# Underwater_vehicle.net
KiCad netlist of a schematic drawn in Altium Designer
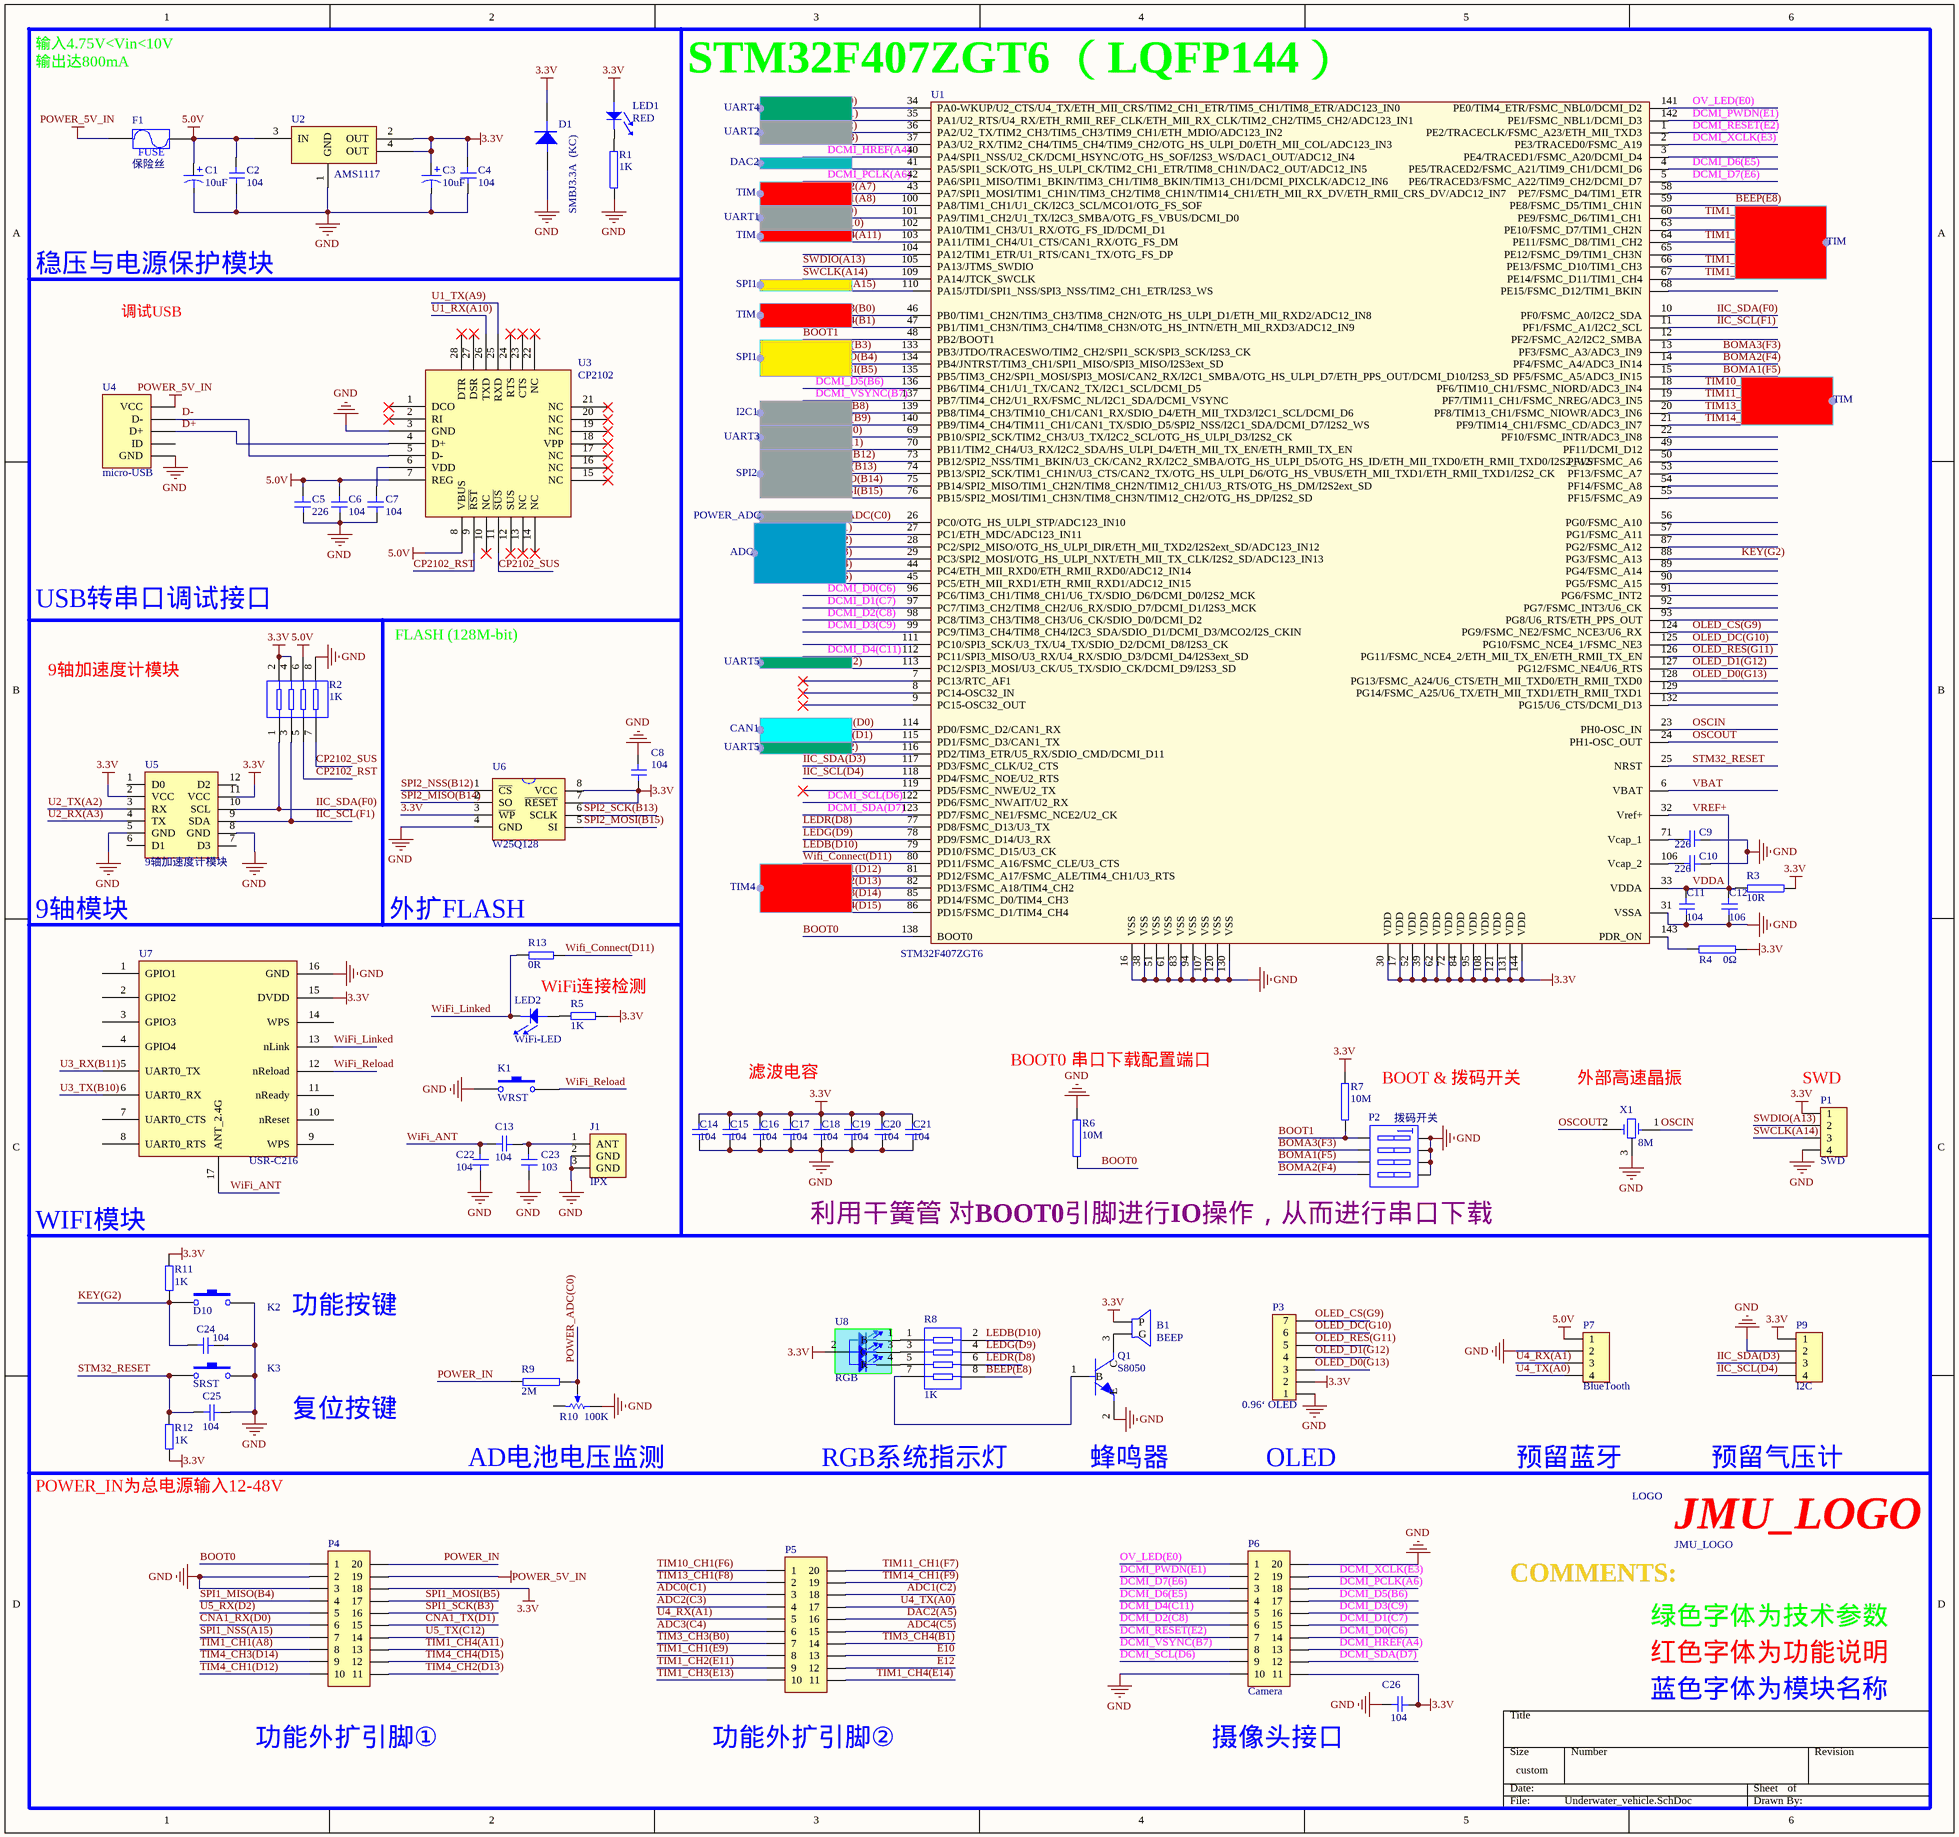
[diagram p0: Underwater_vehicle.SchDoc]

(export (version "E")
  (design (tool "Eeschema 10.0.6"))
  (components
    (comp (ref "B1") (value "BEEP") (footprint "BUZZER") (libsource (lib "EXPLORER") (part "BEEP")))
    (comp (ref "C1")
      (value "10uF")
      (footprint "TAJ-A")
      (description "极性贴片电容")
      (libsource (lib "集大电协1.1.0") (part "Pol Cap"))
    )
    (comp (ref "C2")
      (value "104")
      (footprint "0805C")
      (description "无极贴片电容")
      (libsource (lib "集大电协1.1.0") (part "Cap1"))
    )
    (comp (ref "C3")
      (value "10uF")
      (footprint "TAJ-A")
      (description "极性贴片电容")
      (libsource (lib "集大电协1.1.0") (part "Pol Cap"))
    )
    (comp (ref "C4")
      (value "104")
      (footprint "0805C")
      (description "无极贴片电容")
      (libsource (lib "集大电协1.1.0") (part "Cap1"))
    )
    (comp (ref "C5")
      (value "226")
      (footprint "0805C")
      (description "无极贴片电容")
      (libsource (lib "集大电协1.1.0") (part "Cap1"))
    )
    (comp (ref "C6")
      (value "104")
      (footprint "0805C")
      (description "无极贴片电容")
      (libsource (lib "集大电协1.1.0") (part "Cap1"))
    )
    (comp (ref "C7")
      (value "104")
      (footprint "0805C")
      (description "无极贴片电容")
      (libsource (lib "集大电协1.1.0") (part "Cap1"))
    )
    (comp (ref "C8")
      (value "104")
      (footprint "0805C")
      (description "无极贴片电容")
      (libsource (lib "集大电协1.1.0") (part "Cap1"))
    )
    (comp (ref "C9") (value "226") (footprint "0805C") (libsource (lib "窝牛器件封装") (part "C1")))
    (comp (ref "C10") (value "226") (footprint "0805C") (libsource (lib "窝牛器件封装") (part "C1")))
    (comp (ref "C11") (value "104") (footprint "0805C") (libsource (lib "窝牛器件封装") (part "C1")))
    (comp (ref "C12") (value "106") (footprint "0805C") (libsource (lib "窝牛器件封装") (part "C1")))
    (comp (ref "C13")
      (value "104")
      (footprint "0805C")
      (description "无极贴片电容")
      (libsource (lib "集大电协1.1.2") (part "Cap1"))
    )
    (comp (ref "C14") (value "104") (footprint "0805C") (libsource (lib "窝牛器件封装") (part "C1")))
    (comp (ref "C15") (value "104") (footprint "0805C") (libsource (lib "窝牛器件封装") (part "C1")))
    (comp (ref "C16") (value "104") (footprint "0805C") (libsource (lib "窝牛器件封装") (part "C1")))
    (comp (ref "C17") (value "104") (footprint "0805C") (libsource (lib "窝牛器件封装") (part "C1")))
    (comp (ref "C18") (value "104") (footprint "0805C") (libsource (lib "窝牛器件封装") (part "C1")))
    (comp (ref "C19") (value "104") (footprint "0805C") (libsource (lib "窝牛器件封装") (part "C1")))
    (comp (ref "C20") (value "104") (footprint "0805C") (libsource (lib "窝牛器件封装") (part "C1")))
    (comp (ref "C21") (value "104") (footprint "0805C") (libsource (lib "窝牛器件封装") (part "C1")))
    (comp (ref "C22")
      (value "104")
      (footprint "0805C")
      (description "无极贴片电容")
      (libsource (lib "集大电协1.1.2") (part "Cap1"))
    )
    (comp (ref "C23")
      (value "103")
      (footprint "0805C")
      (description "无极贴片电容")
      (libsource (lib "集大电协1.1.2") (part "Cap1"))
    )
    (comp (ref "C24") (value "104") (footprint "0805C") (libsource (lib "窝牛器件封装") (part "C1")))
    (comp (ref "C25") (value "104") (footprint "0805C") (libsource (lib "窝牛器件封装") (part "C1")))
    (comp (ref "C26")
      (value "104")
      (footprint "0805C")
      (description "无极贴片电容")
      (libsource (lib "集大电协1.1.5") (part "Cap1"))
    )
    (comp (ref "D1")
      (value "SMBJ3.3A  (KC)")
      (footprint "SMBJ")
      (description "二极管")
      (libsource (lib "集大电协1.1.0") (part "Diode"))
    )
    (comp (ref "F1") (value "保险丝") (footprint "1812") (libsource (lib "集大电协1.1.2") (part "Fuse")))
    (comp (ref "J1") (value "IPX") (footprint "IPX天线底座") (libsource (lib "集大电协1.1.2") (part "IPX天线座")))
    (comp (ref "K1")
      (value "WRST")
      (footprint "贴片按键")
      (description "轻触开关")
      (libsource (lib "集大电协1.1.2") (part "轻触按键"))
    )
    (comp (ref "K2") (value "D10") (footprint "贴片按键") (libsource (lib "窝牛器件封装") (part "Key(两脚贴片)")))
    (comp (ref "K3") (value "SRST") (footprint "贴片按键") (libsource (lib "窝牛器件封装") (part "Key(两脚贴片)")))
    (comp (ref "LED1")
      (value "RED")
      (footprint "0805LED(RED)")
      (description "发光二极管")
      (libsource (lib "集大电协1.1.2") (part "LED"))
    )
    (comp (ref "LED2")
      (value "WiFi-LED")
      (footprint "0805LED(GREEN)")
      (description "发光二极管")
      (libsource (lib "集大电协1.1.2") (part "LED"))
    )
    (comp (ref "LOGO")
      (value "JMU_LOGO")
      (footprint "JMU_LOGO(1.35cm)")
      (description "LOGO")
      (libsource (lib "集大电协1.1.5") (part "JMU_LOGO"))
    )
    (comp (ref "P1")
      (value "SWD")
      (footprint "Header 4")
      (description "排针")
      (libsource (lib "集大电协1.1.0") (part "Header 4"))
    )
    (comp (ref "P2")
      (value "拨码开关")
      (footprint "拨码开关(4位贴片)")
      (description "4位拨码开关")
      (libsource (lib "集大电协1.1.2") (part "拨码开关4"))
    )
    (comp (ref "P3")
      (value "0.96‘ OLED")
      (footprint "Header 7")
      (description "排针")
      (libsource (lib "集大电协1.1.5") (part "Header 7"))
    )
    (comp (ref "P4") (value "~") (footprint "Header 10X2") (libsource (lib "集大电协1.1.2") (part "Header 10X2")))
    (comp (ref "P5") (value "~") (footprint "Header 10X2") (libsource (lib "集大电协1.1.2") (part "Header 10X2")))
    (comp (ref "P6")
      (value "Camera")
      (footprint "Header 10X2")
      (libsource (lib "集大电协1.1.2") (part "Header 10X2"))
    )
    (comp (ref "P7")
      (value "BlueTooth")
      (footprint "Header 4(排母)")
      (description "排针")
      (libsource (lib "集大电协1.1.5") (part "Header 4"))
    )
    (comp (ref "P9")
      (value "I2C")
      (footprint "Header 4")
      (description "排针")
      (libsource (lib "集大电协1.1.5") (part "Header 4"))
    )
    (comp (ref "Q1")
      (value "S8050")
      (footprint "SOT-23")
      (description "NPN三极管")
      (libsource (lib "集大电协1.1.2") (part "NPN"))
    )
    (comp (ref "R1") (value "1K") (footprint "0805R") (libsource (lib "窝牛器件封装") (part "R1")))
    (comp (ref "R2")
      (value "1K")
      (footprint "排阻(4位贴片)")
      (description "排阻")
      (libsource (lib "集大电协1.1.2") (part "Res-4"))
    )
    (comp (ref "R3") (value "10R") (footprint "0805R") (libsource (lib "窝牛器件封装") (part "R1")))
    (comp (ref "R4") (value "0Ω") (footprint "0805R") (libsource (lib "窝牛器件封装") (part "R1")))
    (comp (ref "R5")
      (value "1K")
      (footprint "0805R")
      (description "电阻")
      (libsource (lib "集大电协1.1.2") (part "Res"))
    )
    (comp (ref "R6") (value "10M") (footprint "0805R") (libsource (lib "窝牛器件封装") (part "R1")))
    (comp (ref "R7") (value "10M") (footprint "0805R") (libsource (lib "窝牛器件封装") (part "R1")))
    (comp (ref "R8")
      (value "1K")
      (footprint "排阻(4位贴片)")
      (description "排阻")
      (libsource (lib "集大电协1.1.2") (part "Res-4"))
    )
    (comp (ref "R9") (value "2M") (footprint "0805R") (libsource (lib "窝牛器件封装") (part "R1")))
    (comp (ref "R10")
      (value "100K")
      (footprint "3296w")
      (description "电位器")
      (libsource (lib "集大电协1.1.2") (part "RPot"))
    )
    (comp (ref "R11")
      (value "1K")
      (footprint "0805R")
      (description "电阻")
      (libsource (lib "集大电协1.1.5") (part "Res"))
    )
    (comp (ref "R12")
      (value "1K")
      (footprint "0805R")
      (description "电阻")
      (libsource (lib "集大电协1.1.5") (part "Res"))
    )
    (comp (ref "R13")
      (value "0R")
      (footprint "0805R")
      (description "电阻")
      (libsource (lib "集大电协1.1.5") (part "Res"))
    )
    (comp (ref "U1")
      (value "STM32F407ZGT6")
      (footprint "LQFP-144")
      (libsource (lib "窝牛器件封装") (part "STM32F407ZET6"))
    )
    (comp (ref "U2")
      (value "AMS1117")
      (footprint "SOT-223")
      (description "电源芯片")
      (libsource (lib "集大电协1.1.0") (part "AMS1117-3.3V/5.0V"))
    )
    (comp (ref "U3")
      (value "CP2102")
      (footprint "QFN-28")
      (description "USB转串口芯片")
      (libsource (lib "集大电协1.1.0") (part "CP2102"))
    )
    (comp (ref "U4")
      (value "micro-USB")
      (footprint "Micro-USB (兼容牛角)")
      (description "USB接口")
      (libsource (lib "集大电协1.1.2") (part "micro-USB"))
    )
    (comp (ref "U5") (value "9轴加速度计模块") (footprint "9轴加速度计") (libsource (lib "窝牛器件封装") (part "9轴加速度计")))
    (comp (ref "U6")
      (value "W25Q128")
      (footprint "SOW-8")
      (description "FLASH芯片")
      (libsource (lib "集大电协1.1.0") (part "W25Q128"))
    )
    (comp (ref "U7")
      (value "USR-C216")
      (footprint "USR-C216")
      (libsource (lib "集大电协1.1.2") (part "USR-C216"))
    )
    (comp (ref "U8") (value "RGB") (footprint "RGB-3528") (libsource (lib "集大电协1.1.2") (part "RGB")))
    (comp (ref "X1") (value "8M") (footprint "三脚贴片8M晶振") (libsource (lib "集大电协1.1.2") (part "XTAL三脚贴片晶振")))
  )
  (nets
    (net (code "1") (name "/ADC0(C1)") (class "Default")
      (node (ref "P5") (pin "3") (pinfunction "3_3") (pintype "passive"))
      (node (ref "U1") (pin "27") (pinfunction "PC1/ETH_MDC/ADC123_IN11_27") (pintype "passive"))
    )
    (net (code "2") (name "/ADC1(C2)") (class "Default")
      (node (ref "P5") (pin "18") (pinfunction "18_18") (pintype "passive"))
      (node (ref "U1") (pin "28") (pinfunction "PC2/SPI2_MISO/OTG_HS_ULPI_DIR/ETH_MII_TXD2/I2S2ext_SD/ADC123_IN12_28") (pintype "passive"))
    )
    (net (code "3") (name "/ADC2(C3)") (class "Default")
      (node (ref "P5") (pin "4") (pinfunction "4_4") (pintype "passive"))
      (node (ref "U1") (pin "29") (pinfunction "PC3/SPI2_MOSI/OTG_HS_ULPI_NXT/ETH_MII_TX_CLK/I2S2_SD/ADC123_IN13_29") (pintype "passive"))
    )
    (net (code "4") (name "/ADC3(C4)") (class "Default")
      (node (ref "P5") (pin "6") (pinfunction "6_6") (pintype "passive"))
      (node (ref "U1") (pin "44") (pinfunction "PC4/ETH_MII_RXD0/ETH_RMII_RXD0/ADC12_IN14_44") (pintype "passive"))
    )
    (net (code "5") (name "/ADC4(C5)") (class "Default")
      (node (ref "P5") (pin "15") (pinfunction "15_15") (pintype "passive"))
      (node (ref "U1") (pin "45") (pinfunction "PC5/ETH_MII_RXD1/ETH_RMII_RXD1/ADC12_IN15_45") (pintype "passive"))
    )
    (net (code "6") (name "/BEEP(E8)") (class "Default")
      (node (ref "R8") (pin "8") (pinfunction "8_8") (pintype "passive"))
      (node (ref "U1") (pin "59") (pinfunction "PE8/FSMC_D5/TIM1_CH1N_59") (pintype "passive"))
    )
    (net (code "7") (name "/BOMA1(F5)") (class "Default")
      (node (ref "P2") (pin "3") (pinfunction "A3_3") (pintype "passive"))
      (node (ref "U1") (pin "15") (pinfunction "PF5/FSMC_A5/ADC3_IN15_15") (pintype "passive"))
    )
    (net (code "8") (name "/BOMA2(F4)") (class "Default")
      (node (ref "P2") (pin "4") (pinfunction "A4_4") (pintype "passive"))
      (node (ref "U1") (pin "14") (pinfunction "PF4/FSMC_A4/ADC3_IN14_14") (pintype "passive"))
    )
    (net (code "9") (name "/BOMA3(F3)") (class "Default")
      (node (ref "P2") (pin "2") (pinfunction "A2_2") (pintype "passive"))
      (node (ref "U1") (pin "13") (pinfunction "PF3/FSMC_A3/ADC3_IN9_13") (pintype "passive"))
    )
    (net (code "10") (name "/BOOT0") (class "Default")
      (node (ref "P4") (pin "1") (pinfunction "1_1") (pintype "passive"))
      (node (ref "R6") (pin "1") (pinfunction "1_1") (pintype "passive"))
      (node (ref "U1") (pin "138") (pinfunction "BOOT0_138") (pintype "passive"))
    )
    (net (code "11") (name "/BOOT1") (class "Default")
      (node (ref "P2") (pin "1") (pinfunction "A1_1") (pintype "passive"))
      (node (ref "R7") (pin "1") (pinfunction "1_1") (pintype "passive"))
      (node (ref "U1") (pin "48") (pinfunction "PB2/BOOT1_48") (pintype "passive"))
    )
    (net (code "12") (name "/CNA1_RX(D0)") (class "Default")
      (node (ref "P4") (pin "6") (pinfunction "6_6") (pintype "passive"))
      (node (ref "U1") (pin "114") (pinfunction "PD0/FSMC_D2/CAN1_RX_114") (pintype "passive"))
    )
    (net (code "13") (name "/CNA1_TX(D1)") (class "Default")
      (node (ref "P4") (pin "15") (pinfunction "15_15") (pintype "passive"))
      (node (ref "U1") (pin "115") (pinfunction "PD1/FSMC_D3/CAN1_TX_115") (pintype "passive"))
    )
    (net (code "14") (name "/CP2102_RST") (class "Default")
      (node (ref "R2") (pin "5") (pinfunction "5_5") (pintype "passive"))
      (node (ref "U3") (pin "9") (pinfunction "~{RST}_9") (pintype "passive"))
    )
    (net (code "15") (name "/CP2102_SUS") (class "Default")
      (node (ref "R2") (pin "7") (pinfunction "7_7") (pintype "passive"))
      (node (ref "U3") (pin "11") (pinfunction "~{SUS}_11") (pintype "passive"))
    )
    (net (code "16") (name "/D+") (class "Default")
      (node (ref "U3") (pin "4") (pinfunction "D+_4") (pintype "passive"))
      (node (ref "U4") (pin "3") (pinfunction "D+_3") (pintype "power_in"))
    )
    (net (code "17") (name "/D-") (class "Default")
      (node (ref "U3") (pin "5") (pinfunction "D-_5") (pintype "passive"))
      (node (ref "U4") (pin "2") (pinfunction "D-_2") (pintype "power_in"))
    )
    (net (code "18") (name "/DAC2(A5)") (class "Default")
      (node (ref "P5") (pin "16") (pinfunction "16_16") (pintype "passive"))
      (node (ref "U1") (pin "41") (pinfunction "PA5/SPI1_SCK/OTG_HS_ULPI_CK/TIM2_CH1_ETR/TIM8_CH1N/DAC2_OUT/ADC12_IN5_41") (pintype "passive"))
    )
    (net (code "19") (name "/DCMI_D0(C6)") (class "Default")
      (node (ref "P6") (pin "14") (pinfunction "14_14") (pintype "passive"))
      (node (ref "U1") (pin "96") (pinfunction "PC6/TIM3_CH1/TIM8_CH1/U6_TX/SDIO_D6/DCMI_D0/I2S2_MCK_96") (pintype "passive"))
    )
    (net (code "20") (name "/DCMI_D1(C7)") (class "Default")
      (node (ref "P6") (pin "15") (pinfunction "15_15") (pintype "passive"))
      (node (ref "U1") (pin "97") (pinfunction "PC7/TIM3_CH2/TIM8_CH2/U6_RX/SDIO_D7/DCMI_D1/I2S3_MCK_97") (pintype "passive"))
    )
    (net (code "21") (name "/DCMI_D2(C8)") (class "Default")
      (node (ref "P6") (pin "6") (pinfunction "6_6") (pintype "passive"))
      (node (ref "U1") (pin "98") (pinfunction "PC8/TIM3_CH3/TIM8_CH3/U6_CK/SDIO_D0/DCMI_D2_98") (pintype "passive"))
    )
    (net (code "22") (name "/DCMI_D3(C9)") (class "Default")
      (node (ref "P6") (pin "16") (pinfunction "16_16") (pintype "passive"))
      (node (ref "U1") (pin "99") (pinfunction "PC9/TIM3_CH4/TIM8_CH4/I2C3_SDA/SDIO_D1/DCMI_D3/MCO2/I2S_CKIN_99") (pintype "passive"))
    )
    (net (code "23") (name "/DCMI_D4(C11)") (class "Default")
      (node (ref "P6") (pin "5") (pinfunction "5_5") (pintype "passive"))
      (node (ref "U1") (pin "112") (pinfunction "PC11/SPI3_MISO/U3_RX/U4_RX/SDIO_D3/DCMI_D4/I2S3ext_SD_112") (pintype "passive"))
    )
    (net (code "24") (name "/DCMI_D5(B6)") (class "Default")
      (node (ref "P6") (pin "17") (pinfunction "17_17") (pintype "passive"))
      (node (ref "U1") (pin "136") (pinfunction "PB6/TIM4_CH1/U1_TX/CAN2_TX/I2C1_SCL/DCMI_D5_136") (pintype "passive"))
    )
    (net (code "25") (name "/DCMI_D6(E5)") (class "Default")
      (node (ref "P6") (pin "4") (pinfunction "4_4") (pintype "passive"))
      (node (ref "U1") (pin "4") (pinfunction "PE5/TRACED2/FSMC_A21/TIM9_CH1/DCMI_D6_4") (pintype "passive"))
    )
    (net (code "26") (name "/DCMI_D7(E6)") (class "Default")
      (node (ref "P6") (pin "3") (pinfunction "3_3") (pintype "passive"))
      (node (ref "U1") (pin "5") (pinfunction "PE6/TRACED3/FSMC_A22/TIM9_CH2/DCMI_D7_5") (pintype "passive"))
    )
    (net (code "27") (name "/DCMI_HREF(A4)") (class "Default")
      (node (ref "P6") (pin "13") (pinfunction "13_13") (pintype "passive"))
      (node (ref "U1") (pin "40") (pinfunction "PA4/SPI1_NSS/U2_CK/DCMI_HSYNC/OTG_HS_SOF/I2S3_WS/DAC1_OUT/ADC12_IN4_40") (pintype "passive"))
    )
    (net (code "28") (name "/DCMI_PCLK(A6)") (class "Default")
      (node (ref "P6") (pin "18") (pinfunction "18_18") (pintype "passive"))
      (node (ref "U1") (pin "42") (pinfunction "PA6/SPI1_MISO/TIM1_BKIN/TIM3_CH1/TIM8_BKIN/TIM13_CH1/DCMI_PIXCLK/ADC12_IN6_42") (pintype "passive"))
    )
    (net (code "29") (name "/DCMI_PWDN(E1)") (class "Default")
      (node (ref "P6") (pin "2") (pinfunction "2_2") (pintype "passive"))
      (node (ref "U1") (pin "142") (pinfunction "PE1/FSMC_NBL1/DCMI_D3_142") (pintype "passive"))
    )
    (net (code "30") (name "/DCMI_RESET(E2)") (class "Default")
      (node (ref "P6") (pin "7") (pinfunction "7_7") (pintype "passive"))
      (node (ref "U1") (pin "1") (pinfunction "PE2/TRACECLK/FSMC_A23/ETH_MII_TXD3_1") (pintype "passive"))
    )
    (net (code "31") (name "/DCMI_SCL(D6)") (class "Default")
      (node (ref "P6") (pin "9") (pinfunction "9_9") (pintype "passive"))
      (node (ref "U1") (pin "122") (pinfunction "PD6/FSMC_NWAIT/U2_RX_122") (pintype "passive"))
    )
    (net (code "32") (name "/DCMI_SDA(D7)") (class "Default")
      (node (ref "P6") (pin "12") (pinfunction "12_12") (pintype "passive"))
      (node (ref "U1") (pin "123") (pinfunction "PD7/FSMC_NE1/FSMC_NCE2/U2_CK_123") (pintype "passive"))
    )
    (net (code "33") (name "/DCMI_VSYNC(B7)") (class "Default")
      (node (ref "P6") (pin "8") (pinfunction "8_8") (pintype "passive"))
      (node (ref "U1") (pin "137") (pinfunction "PB7/TIM4_CH2/U1_RX/FSMC_NL/I2C1_SDA/DCMI_VSYNC_137") (pintype "passive"))
    )
    (net (code "34") (name "/DCMI_XCLK(E3)") (class "Default")
      (node (ref "P6") (pin "19") (pinfunction "19_19") (pintype "passive"))
      (node (ref "U1") (pin "2") (pinfunction "PE3/TRACED0/FSMC_A19_2") (pintype "passive"))
    )
    (net (code "35") (name "/E10") (class "Default")
      (node (ref "P5") (pin "13") (pinfunction "13_13") (pintype "passive"))
      (node (ref "U1") (pin "63") (pinfunction "PE10/FSMC_D7/TIM1_CH2N_63") (pintype "passive"))
    )
    (net (code "36") (name "/E12") (class "Default")
      (node (ref "P5") (pin "12") (pinfunction "12_12") (pintype "passive"))
      (node (ref "U1") (pin "65") (pinfunction "PE12/FSMC_D9/TIM1_CH3N_65") (pintype "passive"))
    )
    (net (code "37") (name "/IIC1_SCL(B8)") (class "Default")
      (node (ref "U1") (pin "139") (pinfunction "PB8/TIM4_CH3/TIM10_CH1/CAN1_RX/SDIO_D4/ETH_MII_TXD3/I2C1_SCL/DCMI_D6_139") (pintype "passive"))
    )
    (net (code "38") (name "/IIC1_SDA(B9)") (class "Default")
      (node (ref "U1") (pin "140") (pinfunction "PB9/TIM4_CH4/TIM11_CH1/CAN1_TX/SDIO_D5/SPI2_NSS/I2C1_SDA/DCMI_D7/I2S2_WS_140") (pintype "passive"))
    )
    (net (code "39") (name "/IIC_SCL(D4)") (class "Default")
      (node (ref "P9") (pin "4") (pinfunction "4_4") (pintype "passive"))
      (node (ref "U1") (pin "118") (pinfunction "PD4/FSMC_NOE/U2_RTS_118") (pintype "passive"))
    )
    (net (code "40") (name "/IIC_SCL(F1)") (class "Default")
      (node (ref "R2") (pin "3") (pinfunction "3_3") (pintype "passive"))
      (node (ref "U1") (pin "11") (pinfunction "PF1/FSMC_A1/I2C2_SCL_11") (pintype "passive"))
      (node (ref "U5") (pin "9") (pinfunction "SDA_9") (pintype "passive"))
    )
    (net (code "41") (name "/IIC_SDA(D3)") (class "Default")
      (node (ref "P9") (pin "3") (pinfunction "3_3") (pintype "passive"))
      (node (ref "U1") (pin "117") (pinfunction "PD3/FSMC_CLK/U2_CTS_117") (pintype "passive"))
    )
    (net (code "42") (name "/IIC_SDA(F0)") (class "Default")
      (node (ref "R2") (pin "1") (pinfunction "1_1") (pintype "passive"))
      (node (ref "U1") (pin "10") (pinfunction "PF0/FSMC_A0/I2C2_SDA_10") (pintype "passive"))
      (node (ref "U5") (pin "10") (pinfunction "SCL_10") (pintype "passive"))
    )
    (net (code "43") (name "/KEY(G2)") (class "Default")
      (node (ref "C24") (pin "1") (pinfunction "1_1") (pintype "passive"))
      (node (ref "K2") (pin "1") (pinfunction "1_1") (pintype "passive"))
      (node (ref "R11") (pin "1") (pinfunction "1_1") (pintype "passive"))
      (node (ref "U1") (pin "88") (pinfunction "PG3/FSMC_A13_88") (pintype "passive"))
    )
    (net (code "44") (name "/LEDB(D10)") (class "Default")
      (node (ref "R8") (pin "2") (pinfunction "2_2") (pintype "passive"))
      (node (ref "U1") (pin "79") (pinfunction "PD10/FSMC_D15/U3_CK_79") (pintype "passive"))
    )
    (net (code "45") (name "/LEDG(D9)") (class "Default")
      (node (ref "R8") (pin "4") (pinfunction "4_4") (pintype "passive"))
      (node (ref "U1") (pin "78") (pinfunction "PD9/FSMC_D14/U3_RX_78") (pintype "passive"))
    )
    (net (code "46") (name "/LEDR(D8)") (class "Default")
      (node (ref "R8") (pin "6") (pinfunction "6_6") (pintype "passive"))
      (node (ref "U1") (pin "77") (pinfunction "PD8/FSMC_D13/U3_TX_77") (pintype "passive"))
    )
    (net (code "47") (name "/OLED_CS(G9)") (class "Default")
      (node (ref "P3") (pin "7") (pinfunction "7_7") (pintype "passive"))
      (node (ref "U1") (pin "124") (pinfunction "PG9/FSMC_NE2/FSMC_NCE3/U6_RX_124") (pintype "passive"))
    )
    (net (code "48") (name "/OLED_D0(G13)") (class "Default")
      (node (ref "P3") (pin "3") (pinfunction "3_3") (pintype "passive"))
      (node (ref "U1") (pin "128") (pinfunction "PG13/FSMC_A24/U6_CTS/ETH_MII_TXD0/ETH_RMII_TXD0_128") (pintype "passive"))
    )
    (net (code "49") (name "/OLED_D1(G12)") (class "Default")
      (node (ref "P3") (pin "4") (pinfunction "4_4") (pintype "passive"))
      (node (ref "U1") (pin "127") (pinfunction "PG12/FSMC_NE4/U6_RTS_127") (pintype "passive"))
    )
    (net (code "50") (name "/OLED_DC(G10)") (class "Default")
      (node (ref "P3") (pin "6") (pinfunction "6_6") (pintype "passive"))
      (node (ref "U1") (pin "125") (pinfunction "PG10/FSMC_NCE4_1/FSMC_NE3_125") (pintype "passive"))
    )
    (net (code "51") (name "/OLED_RES(G11)") (class "Default")
      (node (ref "P3") (pin "5") (pinfunction "5_5") (pintype "passive"))
      (node (ref "U1") (pin "126") (pinfunction "PG11/FSMC_NCE4_2/ETH_MII_TX_EN/ETH_RMII_TX_EN_126") (pintype "passive"))
    )
    (net (code "52") (name "/OSCIN") (class "Default")
      (node (ref "U1") (pin "23") (pinfunction "PH0-OSC_IN_23") (pintype "passive"))
      (node (ref "X1") (pin "1") (pinfunction "1_1") (pintype "passive"))
    )
    (net (code "53") (name "/OSCOUT") (class "Default")
      (node (ref "U1") (pin "24") (pinfunction "PH1-OSC_OUT_24") (pintype "passive"))
      (node (ref "X1") (pin "2") (pinfunction "2_2") (pintype "passive"))
    )
    (net (code "54") (name "/OV_LED(E0)") (class "Default")
      (node (ref "P6") (pin "1") (pinfunction "1_1") (pintype "passive"))
      (node (ref "U1") (pin "141") (pinfunction "PE0/TIM4_ETR/FSMC_NBL0/DCMI_D2_141") (pintype "passive"))
    )
    (net (code "55") (name "/POWER_ADC(C0)") (class "Default")
      (node (ref "R10") (pin "2") (pinfunction "TAP_2") (pintype "passive"))
      (node (ref "R9") (pin "2") (pinfunction "2_2") (pintype "passive"))
      (node (ref "U1") (pin "26") (pinfunction "PC0/OTG_HS_ULPI_STP/ADC123_IN10_26") (pintype "passive"))
    )
    (net (code "56") (name "/POWER_IN") (class "Default")
      (node (ref "P4") (pin "20") (pinfunction "20_20") (pintype "passive"))
      (node (ref "R9") (pin "1") (pinfunction "1_1") (pintype "passive"))
    )
    (net (code "57") (name "/SPI1_MISO(B4)") (class "Default")
      (node (ref "P4") (pin "4") (pinfunction "4_4") (pintype "passive"))
      (node (ref "U1") (pin "134") (pinfunction "PB4/JNTRST/TIM3_CH1/SPI1_MISO/SPI3_MISO/I2S3ext_SD_134") (pintype "passive"))
    )
    (net (code "58") (name "/SPI1_MOSI(B5)") (class "Default")
      (node (ref "P4") (pin "17") (pinfunction "17_17") (pintype "passive"))
      (node (ref "U1") (pin "135") (pinfunction "PB5/TIM3_CH2/SPI1_MOSI/SPI3_MOSI/CAN2_RX/I2C1_SMBA/OTG_HS_ULPI_D7/ETH_PPS_OUT/DCMI_D10/I2S3_SD_135") (pintype "passive"))
    )
    (net (code "59") (name "/SPI1_NSS(A15)") (class "Default")
      (node (ref "P4") (pin "7") (pinfunction "7_7") (pintype "passive"))
      (node (ref "U1") (pin "110") (pinfunction "PA15/JTDI/SPI1_NSS/SPI3_NSS/TIM2_CH1_ETR/I2S3_WS_110") (pintype "passive"))
    )
    (net (code "60") (name "/SPI1_SCK(B3)") (class "Default")
      (node (ref "P4") (pin "16") (pinfunction "16_16") (pintype "passive"))
      (node (ref "U1") (pin "133") (pinfunction "PB3/JTDO/TRACESWO/TIM2_CH2/SPI1_SCK/SPI3_SCK/I2S3_CK_133") (pintype "passive"))
    )
    (net (code "61") (name "/SPI2_MISO(B14)") (class "Default")
      (node (ref "U1") (pin "75") (pinfunction "PB14/SPI2_MISO/TIM1_CH2N/TIM8_CH2N/TIM12_CH1/U3_RTS/OTG_HS_DM/I2S2ext_SD_75") (pintype "passive"))
      (node (ref "U6") (pin "2") (pinfunction "SO_2") (pintype "passive"))
    )
    (net (code "62") (name "/SPI2_MOSI(B15)") (class "Default")
      (node (ref "U1") (pin "76") (pinfunction "PB15/SPI2_MOSI/TIM1_CH3N/TIM8_CH3N/TIM12_CH2/OTG_HS_DP/I2S2_SD_76") (pintype "passive"))
      (node (ref "U6") (pin "5") (pinfunction "SI_5") (pintype "passive"))
    )
    (net (code "63") (name "/SPI2_NSS(B12)") (class "Default")
      (node (ref "U1") (pin "73") (pinfunction "PB12/SPI2_NSS/TIM1_BKIN/U3_CK/CAN2_RX/I2C2_SMBA/OTG_HS_ULPI_D5/OTG_HS_ID/ETH_MII_TXD0/ETH_RMII_TXD0/I2S2_WS_73") (pintype "passive"))
      (node (ref "U6") (pin "1") (pinfunction "~{CS}_1") (pintype "passive"))
    )
    (net (code "64") (name "/SPI2_SCK(B13)") (class "Default")
      (node (ref "U1") (pin "74") (pinfunction "PB13/SPI2_SCK/TIM1_CH1N/U3_CTS/CAN2_TX/OTG_HS_ULPI_D6/OTG_HS_VBUS/ETH_MII_TXD1/ETH_RMII_TXD1/I2S2_CK_74") (pintype "passive"))
      (node (ref "U6") (pin "6") (pinfunction "SCLK_6") (pintype "passive"))
    )
    (net (code "65") (name "/STM32_RESET") (class "Default")
      (node (ref "C25") (pin "1") (pinfunction "1_1") (pintype "passive"))
      (node (ref "K3") (pin "1") (pinfunction "1_1") (pintype "passive"))
      (node (ref "R12") (pin "2") (pinfunction "2_2") (pintype "passive"))
      (node (ref "U1") (pin "25") (pinfunction "NRST_25") (pintype "passive"))
    )
    (net (code "66") (name "/SWCLK(A14)") (class "Default")
      (node (ref "P1") (pin "3") (pinfunction "3_3") (pintype "passive"))
      (node (ref "U1") (pin "109") (pinfunction "PA14/JTCK_SWCLK_109") (pintype "passive"))
    )
    (net (code "67") (name "/SWDIO(A13)") (class "Default")
      (node (ref "P1") (pin "2") (pinfunction "2_2") (pintype "passive"))
      (node (ref "U1") (pin "105") (pinfunction "PA13/JTMS_SWDIO_105") (pintype "passive"))
    )
    (net (code "68") (name "/TIM1_CH1(A8)") (class "Default")
      (node (ref "P4") (pin "8") (pinfunction "8_8") (pintype "passive"))
      (node (ref "U1") (pin "100") (pinfunction "PA8/TIM1_CH1/U1_CK/I2C3_SCL/MCO1/OTG_FS_SOF_100") (pintype "passive"))
    )
    (net (code "69") (name "/TIM1_CH1(E9)") (class "Default")
      (node (ref "P5") (pin "8") (pinfunction "8_8") (pintype "passive"))
      (node (ref "U1") (pin "60") (pinfunction "PE9/FSMC_D6/TIM1_CH1_60") (pintype "passive"))
    )
    (net (code "70") (name "/TIM1_CH2(E11)") (class "Default")
      (node (ref "P5") (pin "9") (pinfunction "9_9") (pintype "passive"))
      (node (ref "U1") (pin "64") (pinfunction "PE11/FSMC_D8/TIM1_CH2_64") (pintype "passive"))
    )
    (net (code "71") (name "/TIM1_CH3(E13)") (class "Default")
      (node (ref "P5") (pin "10") (pinfunction "10_10") (pintype "passive"))
      (node (ref "U1") (pin "66") (pinfunction "PE13/FSMC_D10/TIM1_CH3_66") (pintype "passive"))
    )
    (net (code "72") (name "/TIM1_CH4(A11)") (class "Default")
      (node (ref "P4") (pin "13") (pinfunction "13_13") (pintype "passive"))
      (node (ref "U1") (pin "103") (pinfunction "PA11/TIM1_CH4/U1_CTS/CAN1_RX/OTG_FS_DM_103") (pintype "passive"))
    )
    (net (code "73") (name "/TIM1_CH4(E14)") (class "Default")
      (node (ref "P5") (pin "11") (pinfunction "11_11") (pintype "passive"))
      (node (ref "U1") (pin "67") (pinfunction "PE14/FSMC_D11/TIM1_CH4_67") (pintype "passive"))
    )
    (net (code "74") (name "/TIM3_CH2(A7)") (class "Default")
      (node (ref "U1") (pin "43") (pinfunction "PA7/SPI1_MOSI/TIM1_CH1N/TIM3_CH2/TIM8_CH1N/TIM14_CH1/ETH_MII_RX_DV/ETH_RMII_CRS_DV/ADC12_IN7_43") (pintype "passive"))
    )
    (net (code "75") (name "/TIM3_CH3(B0)") (class "Default")
      (node (ref "P5") (pin "7") (pinfunction "7_7") (pintype "passive"))
      (node (ref "U1") (pin "46") (pinfunction "PB0/TIM1_CH2N/TIM3_CH3/TIM8_CH2N/OTG_HS_ULPI_D1/ETH_MII_RXD2/ADC12_IN8_46") (pintype "passive"))
    )
    (net (code "76") (name "/TIM3_CH4(B1)") (class "Default")
      (node (ref "P5") (pin "14") (pinfunction "14_14") (pintype "passive"))
      (node (ref "U1") (pin "47") (pinfunction "PB1/TIM1_CH3N/TIM3_CH4/TIM8_CH3N/OTG_HS_INTN/ETH_MII_RXD3/ADC12_IN9_47") (pintype "passive"))
    )
    (net (code "77") (name "/TIM4_CH1(D12)") (class "Default")
      (node (ref "P4") (pin "10") (pinfunction "10_10") (pintype "passive"))
      (node (ref "U1") (pin "81") (pinfunction "PD12/FSMC_A17/FSMC_ALE/TIM4_CH1/U3_RTS_81") (pintype "passive"))
    )
    (net (code "78") (name "/TIM4_CH2(D13)") (class "Default")
      (node (ref "P4") (pin "11") (pinfunction "11_11") (pintype "passive"))
      (node (ref "U1") (pin "82") (pinfunction "PD13/FSMC_A18/TIM4_CH2_82") (pintype "passive"))
    )
    (net (code "79") (name "/TIM4_CH3(D14)") (class "Default")
      (node (ref "P4") (pin "9") (pinfunction "9_9") (pintype "passive"))
      (node (ref "U1") (pin "85") (pinfunction "PD14/FSMC_D0/TIM4_CH3_85") (pintype "passive"))
    )
    (net (code "80") (name "/TIM4_CH4(D15)") (class "Default")
      (node (ref "P4") (pin "12") (pinfunction "12_12") (pintype "passive"))
      (node (ref "U1") (pin "86") (pinfunction "PD15/FSMC_D1/TIM4_CH4_86") (pintype "passive"))
    )
    (net (code "81") (name "/TIM10_CH1(F6)") (class "Default")
      (node (ref "P5") (pin "1") (pinfunction "1_1") (pintype "passive"))
      (node (ref "U1") (pin "18") (pinfunction "PF6/TIM10_CH1/FSMC_NIORD/ADC3_IN4_18") (pintype "passive"))
    )
    (net (code "82") (name "/TIM11_CH1(F7)") (class "Default")
      (node (ref "P5") (pin "20") (pinfunction "20_20") (pintype "passive"))
      (node (ref "U1") (pin "19") (pinfunction "PF7/TIM11_CH1/FSMC_NREG/ADC3_IN5_19") (pintype "passive"))
    )
    (net (code "83") (name "/TIM13_CH1(F8)") (class "Default")
      (node (ref "P5") (pin "2") (pinfunction "2_2") (pintype "passive"))
      (node (ref "U1") (pin "20") (pinfunction "PF8/TIM13_CH1/FSMC_NIOWR/ADC3_IN6_20") (pintype "passive"))
    )
    (net (code "84") (name "/TIM14_CH1(F9)") (class "Default")
      (node (ref "P5") (pin "19") (pinfunction "19_19") (pintype "passive"))
      (node (ref "U1") (pin "21") (pinfunction "PF9/TIM14_CH1/FSMC_CD/ADC3_IN7_21") (pintype "passive"))
    )
    (net (code "85") (name "/U1_RX(A10)") (class "Default")
      (node (ref "U1") (pin "102") (pinfunction "PA10/TIM1_CH3/U1_RX/OTG_FS_ID/DCMI_D1_102") (pintype "passive"))
      (node (ref "U3") (pin "26") (pinfunction "TXD_26") (pintype "passive"))
    )
    (net (code "86") (name "/U1_TX(A9)") (class "Default")
      (node (ref "U1") (pin "101") (pinfunction "PA9/TIM1_CH2/U1_TX/I2C3_SMBA/OTG_FS_VBUS/DCMI_D0_101") (pintype "passive"))
      (node (ref "U3") (pin "25") (pinfunction "RXD_25") (pintype "passive"))
    )
    (net (code "87") (name "/U2_RX(A3)") (class "Default")
      (node (ref "U1") (pin "37") (pinfunction "PA3/U2_RX/TIM2_CH4/TIM5_CH4/TIM9_CH2/OTG_HS_ULPI_D0/ETH_MII_COL/ADC123_IN3_37") (pintype "passive"))
      (node (ref "U5") (pin "4") (pinfunction "TX_4") (pintype "passive"))
    )
    (net (code "88") (name "/U2_TX(A2)") (class "Default")
      (node (ref "U1") (pin "36") (pinfunction "PA2/U2_TX/TIM2_CH3/TIM5_CH3/TIM9_CH1/ETH_MDIO/ADC123_IN2_36") (pintype "passive"))
      (node (ref "U5") (pin "3") (pinfunction "RX_3") (pintype "passive"))
    )
    (net (code "89") (name "/U3_RX(B11)") (class "Default")
      (node (ref "U1") (pin "70") (pinfunction "PB11/TIM2_CH4/U3_RX/I2C2_SDA/HS_ULPI_D4/ETH_MII_TX_EN/ETH_RMII_TX_EN_70") (pintype "passive"))
      (node (ref "U7") (pin "5") (pinfunction "UART0_TX_5") (pintype "passive"))
    )
    (net (code "90") (name "/U3_TX(B10)") (class "Default")
      (node (ref "U1") (pin "69") (pinfunction "PB10/SPI2_SCK/TIM2_CH3/U3_TX/I2C2_SCL/OTG_HS_ULPI_D3/I2S2_CK_69") (pintype "passive"))
      (node (ref "U7") (pin "6") (pinfunction "UART0_RX_6") (pintype "passive"))
    )
    (net (code "91") (name "/U4_RX(A1)") (class "Default")
      (node (ref "P5") (pin "5") (pinfunction "5_5") (pintype "passive"))
      (node (ref "P7") (pin "3") (pinfunction "3_3") (pintype "passive"))
      (node (ref "U1") (pin "35") (pinfunction "PA1/U2_RTS/U4_RX/ETH_RMII_REF_CLK/ETH_MII_RX_CLK/TIM2_CH2/TIM5_CH2/ADC123_IN1_35") (pintype "passive"))
    )
    (net (code "92") (name "/U4_TX(A0)") (class "Default")
      (node (ref "P5") (pin "17") (pinfunction "17_17") (pintype "passive"))
      (node (ref "P7") (pin "4") (pinfunction "4_4") (pintype "passive"))
      (node (ref "U1") (pin "34") (pinfunction "PA0-WKUP/U2_CTS/U4_TX/ETH_MII_CRS/TIM2_CH1_ETR/TIM5_CH1/TIM8_ETR/ADC123_IN0_34") (pintype "passive"))
    )
    (net (code "93") (name "/U5_RX(D2)") (class "Default")
      (node (ref "P4") (pin "5") (pinfunction "5_5") (pintype "passive"))
      (node (ref "U1") (pin "116") (pinfunction "PD2/TIM3_ETR/U5_RX/SDIO_CMD/DCMI_D11_116") (pintype "passive"))
    )
    (net (code "94") (name "/U5_TX(C12)") (class "Default")
      (node (ref "P4") (pin "14") (pinfunction "14_14") (pintype "passive"))
      (node (ref "U1") (pin "113") (pinfunction "PC12/SPI3_MOSI/U3_CK/U5_TX/SDIO_CK/DCMI_D9/I2S3_SD_113") (pintype "passive"))
    )
    (net (code "95") (name "/VBAT") (class "Default")
      (node (ref "U1") (pin "6") (pinfunction "VBAT_6") (pintype "passive"))
    )
    (net (code "96") (name "/VDDA") (class "Default")
      (node (ref "C11") (pin "2") (pinfunction "2_2") (pintype "passive"))
      (node (ref "C12") (pin "2") (pinfunction "2_2") (pintype "passive"))
      (node (ref "R3") (pin "1") (pinfunction "1_1") (pintype "passive"))
      (node (ref "U1") (pin "32") (pinfunction "Vref+_32") (pintype "passive"))
      (node (ref "U1") (pin "33") (pinfunction "VDDA_33") (pintype "passive"))
    )
    (net (code "97") (name "/WiFi_ANT") (class "Default")
      (node (ref "C13") (pin "2") (pinfunction "2_2") (pintype "passive"))
      (node (ref "C22") (pin "2") (pinfunction "2_2") (pintype "passive"))
      (node (ref "U7") (pin "17") (pinfunction "ANT_2.4G_17") (pintype "passive"))
    )
    (net (code "98") (name "/WiFi_Linked") (class "Default")
      (node (ref "LED2") (pin "2") (pinfunction "2_2") (pintype "passive"))
      (node (ref "R13") (pin "1") (pinfunction "1_1") (pintype "passive"))
      (node (ref "U7") (pin "13") (pinfunction "nLink_13") (pintype "passive"))
    )
    (net (code "99") (name "/WiFi_Reload") (class "Default")
      (node (ref "K1") (pin "2") (pinfunction "2_2") (pintype "passive"))
      (node (ref "U7") (pin "12") (pinfunction "nReload_12") (pintype "passive"))
    )
    (net (code "100") (name "/Wifi_Connect(D11)") (class "Default")
      (node (ref "R13") (pin "2") (pinfunction "2_2") (pintype "passive"))
      (node (ref "U1") (pin "80") (pinfunction "PD11/FSMC_A16/FSMC_CLE/U3_CTS_80") (pintype "passive"))
    )
    (net (code "101") (name "3.3V") (class "Default")
      (node (ref "B1") (pin "1") (pinfunction "P_1") (pintype "passive"))
      (node (ref "C14") (pin "2") (pinfunction "2_2") (pintype "passive"))
      (node (ref "C15") (pin "2") (pinfunction "2_2") (pintype "passive"))
      (node (ref "C16") (pin "2") (pinfunction "2_2") (pintype "passive"))
      (node (ref "C17") (pin "2") (pinfunction "2_2") (pintype "passive"))
      (node (ref "C18") (pin "2") (pinfunction "2_2") (pintype "passive"))
      (node (ref "C19") (pin "2") (pinfunction "2_2") (pintype "passive"))
      (node (ref "C20") (pin "2") (pinfunction "2_2") (pintype "passive"))
      (node (ref "C21") (pin "2") (pinfunction "2_2") (pintype "passive"))
      (node (ref "C26") (pin "1") (pinfunction "1_1") (pintype "passive"))
      (node (ref "C3") (pin "1") (pinfunction "1_1") (pintype "passive"))
      (node (ref "C4") (pin "2") (pinfunction "2_2") (pintype "passive"))
      (node (ref "C8") (pin "1") (pinfunction "1_1") (pintype "passive"))
      (node (ref "D1") (pin "2") (pinfunction "2_2") (pintype "passive"))
      (node (ref "LED1") (pin "1") (pintype "passive"))
      (node (ref "P1") (pin "1") (pinfunction "1_1") (pintype "passive"))
      (node (ref "P3") (pin "2") (pinfunction "2_2") (pintype "passive"))
      (node (ref "P4") (pin "18") (pinfunction "18_18") (pintype "passive"))
      (node (ref "P6") (pin "11") (pinfunction "11_11") (pintype "passive"))
      (node (ref "P9") (pin "1") (pinfunction "1_1") (pintype "passive"))
      (node (ref "R11") (pin "2") (pinfunction "2_2") (pintype "passive"))
      (node (ref "R12") (pin "1") (pinfunction "1_1") (pintype "passive"))
      (node (ref "R2") (pin "2") (pinfunction "2_2") (pintype "passive"))
      (node (ref "R2") (pin "4") (pinfunction "4_4") (pintype "passive"))
      (node (ref "R3") (pin "2") (pinfunction "2_2") (pintype "passive"))
      (node (ref "R4") (pin "2") (pinfunction "2_2") (pintype "passive"))
      (node (ref "R5") (pin "1") (pinfunction "1_1") (pintype "passive"))
      (node (ref "R7") (pin "2") (pinfunction "2_2") (pintype "passive"))
      (node (ref "U1") (pin "108") (pinfunction "VDD_108") (pintype "passive"))
      (node (ref "U1") (pin "121") (pinfunction "VDD_121") (pintype "passive"))
      (node (ref "U1") (pin "131") (pinfunction "VDD_131") (pintype "passive"))
      (node (ref "U1") (pin "144") (pinfunction "VDD_144") (pintype "passive"))
      (node (ref "U1") (pin "17") (pinfunction "VDD_17") (pintype "passive"))
      (node (ref "U1") (pin "30") (pinfunction "VDD_30") (pintype "passive"))
      (node (ref "U1") (pin "39") (pinfunction "VDD_39") (pintype "passive"))
      (node (ref "U1") (pin "52") (pinfunction "VDD_52") (pintype "passive"))
      (node (ref "U1") (pin "62") (pinfunction "VDD_62") (pintype "passive"))
      (node (ref "U1") (pin "72") (pinfunction "VDD_72") (pintype "passive"))
      (node (ref "U1") (pin "84") (pinfunction "VDD_84") (pintype "passive"))
      (node (ref "U1") (pin "95") (pinfunction "VDD_95") (pintype "passive"))
      (node (ref "U2") (pin "2") (pinfunction "OUT_2") (pintype "passive"))
      (node (ref "U2") (pin "4") (pinfunction "OUT_4") (pintype "passive"))
      (node (ref "U5") (pin "11") (pinfunction "VCC_11") (pintype "passive"))
      (node (ref "U5") (pin "2") (pinfunction "VCC_2") (pintype "passive"))
      (node (ref "U6") (pin "3") (pinfunction "~{WP}_3") (pintype "passive"))
      (node (ref "U6") (pin "7") (pinfunction "~{RESET}_7") (pintype "passive"))
      (node (ref "U6") (pin "8") (pinfunction "VCC_8") (pintype "passive"))
      (node (ref "U7") (pin "15") (pinfunction "DVDD_15") (pintype "passive"))
      (node (ref "U8") (pin "2") (pinfunction "2_2") (pintype "passive"))
    )
    (net (code "102") (name "5.0V") (class "Default")
      (node (ref "C1") (pin "1") (pinfunction "1_1") (pintype "passive"))
      (node (ref "C2") (pin "2") (pinfunction "2_2") (pintype "passive"))
      (node (ref "C5") (pin "1") (pinfunction "1_1") (pintype "passive"))
      (node (ref "C6") (pin "1") (pinfunction "1_1") (pintype "passive"))
      (node (ref "F1") (pin "2") (pinfunction "2_2") (pintype "passive"))
      (node (ref "P7") (pin "1") (pinfunction "1_1") (pintype "passive"))
      (node (ref "R2") (pin "6") (pinfunction "6_6") (pintype "passive"))
      (node (ref "U2") (pin "3") (pinfunction "IN_3") (pintype "passive"))
      (node (ref "U3") (pin "7") (pinfunction "REG_7") (pintype "passive"))
      (node (ref "U3") (pin "8") (pinfunction "VBUS_8") (pintype "passive"))
    )
    (net (code "103") (name "GND") (class "Default")
      (node (ref "C1") (pin "2") (pinfunction "2_2") (pintype "passive"))
      (node (ref "C10") (pin "1") (pinfunction "1_1") (pintype "passive"))
      (node (ref "C11") (pin "1") (pinfunction "1_1") (pintype "passive"))
      (node (ref "C12") (pin "1") (pinfunction "1_1") (pintype "passive"))
      (node (ref "C14") (pin "1") (pinfunction "1_1") (pintype "passive"))
      (node (ref "C15") (pin "1") (pinfunction "1_1") (pintype "passive"))
      (node (ref "C16") (pin "1") (pinfunction "1_1") (pintype "passive"))
      (node (ref "C17") (pin "1") (pinfunction "1_1") (pintype "passive"))
      (node (ref "C18") (pin "1") (pinfunction "1_1") (pintype "passive"))
      (node (ref "C19") (pin "1") (pinfunction "1_1") (pintype "passive"))
      (node (ref "C2") (pin "1") (pinfunction "1_1") (pintype "passive"))
      (node (ref "C20") (pin "1") (pinfunction "1_1") (pintype "passive"))
      (node (ref "C21") (pin "1") (pinfunction "1_1") (pintype "passive"))
      (node (ref "C22") (pin "1") (pinfunction "1_1") (pintype "passive"))
      (node (ref "C23") (pin "1") (pinfunction "1_1") (pintype "passive"))
      (node (ref "C24") (pin "2") (pinfunction "2_2") (pintype "passive"))
      (node (ref "C25") (pin "2") (pinfunction "2_2") (pintype "passive"))
      (node (ref "C26") (pin "2") (pinfunction "2_2") (pintype "passive"))
      (node (ref "C3") (pin "2") (pinfunction "2_2") (pintype "passive"))
      (node (ref "C4") (pin "1") (pinfunction "1_1") (pintype "passive"))
      (node (ref "C5") (pin "2") (pinfunction "2_2") (pintype "passive"))
      (node (ref "C6") (pin "2") (pinfunction "2_2") (pintype "passive"))
      (node (ref "C7") (pin "2") (pinfunction "2_2") (pintype "passive"))
      (node (ref "C8") (pin "2") (pinfunction "2_2") (pintype "passive"))
      (node (ref "C9") (pin "1") (pinfunction "1_1") (pintype "passive"))
      (node (ref "D1") (pin "1") (pintype "passive"))
      (node (ref "J1") (pin "2") (pinfunction "GND_2") (pintype "passive"))
      (node (ref "J1") (pin "3") (pinfunction "GND_3") (pintype "passive"))
      (node (ref "K1") (pin "1") (pinfunction "1_1") (pintype "passive"))
      (node (ref "K2") (pin "2") (pinfunction "2_2") (pintype "passive"))
      (node (ref "K3") (pin "2") (pinfunction "2_2") (pintype "passive"))
      (node (ref "P1") (pin "4") (pinfunction "4_4") (pintype "passive"))
      (node (ref "P2") (pin "5") (pinfunction "B4_5") (pintype "passive"))
      (node (ref "P2") (pin "6") (pinfunction "B3_6") (pintype "passive"))
      (node (ref "P2") (pin "7") (pinfunction "B2_7") (pintype "passive"))
      (node (ref "P2") (pin "8") (pinfunction "B1_8") (pintype "passive"))
      (node (ref "P3") (pin "1") (pinfunction "1_1") (pintype "passive"))
      (node (ref "P4") (pin "2") (pinfunction "2_2") (pintype "passive"))
      (node (ref "P4") (pin "3") (pinfunction "3_3") (pintype "passive"))
      (node (ref "P6") (pin "10") (pinfunction "10_10") (pintype "passive"))
      (node (ref "P6") (pin "20") (pinfunction "20_20") (pintype "passive"))
      (node (ref "P7") (pin "2") (pinfunction "2_2") (pintype "passive"))
      (node (ref "P9") (pin "2") (pinfunction "2_2") (pintype "passive"))
      (node (ref "Q1") (pin "2") (pinfunction "E_2") (pintype "passive"))
      (node (ref "R1") (pin "1") (pinfunction "1_1") (pintype "passive"))
      (node (ref "R10") (pin "1") (pinfunction "TOP_1") (pintype "passive"))
      (node (ref "R2") (pin "8") (pinfunction "8_8") (pintype "passive"))
      (node (ref "R6") (pin "2") (pinfunction "2_2") (pintype "passive"))
      (node (ref "U1") (pin "107") (pinfunction "VSS_107") (pintype "passive"))
      (node (ref "U1") (pin "120") (pinfunction "VSS_120") (pintype "passive"))
      (node (ref "U1") (pin "130") (pinfunction "VSS_130") (pintype "passive"))
      (node (ref "U1") (pin "16") (pinfunction "VSS_16") (pintype "passive"))
      (node (ref "U1") (pin "31") (pinfunction "VSSA_31") (pintype "passive"))
      (node (ref "U1") (pin "38") (pinfunction "VSS_38") (pintype "passive"))
      (node (ref "U1") (pin "51") (pinfunction "VSS_51") (pintype "passive"))
      (node (ref "U1") (pin "61") (pinfunction "VSS_61") (pintype "passive"))
      (node (ref "U1") (pin "83") (pinfunction "VSS_83") (pintype "passive"))
      (node (ref "U1") (pin "94") (pinfunction "VSS_94") (pintype "passive"))
      (node (ref "U2") (pin "1") (pinfunction "GND_1") (pintype "passive"))
      (node (ref "U3") (pin "3") (pinfunction "GND_3") (pintype "passive"))
      (node (ref "U4") (pin "5") (pinfunction "GND_5") (pintype "power_in"))
      (node (ref "U5") (pin "5") (pinfunction "GND_5") (pintype "passive"))
      (node (ref "U5") (pin "8") (pinfunction "GND_8") (pintype "passive"))
      (node (ref "U6") (pin "4") (pinfunction "GND_4") (pintype "passive"))
      (node (ref "U7") (pin "16") (pinfunction "GND_16") (pintype "passive"))
      (node (ref "X1") (pin "3") (pinfunction "3_3") (pintype "passive"))
    )
    (net (code "104") (name "Net-(B1-G)") (class "Default")
      (node (ref "B1") (pin "2") (pinfunction "G_2") (pintype "passive"))
      (node (ref "Q1") (pin "3") (pinfunction "C_3") (pintype "passive"))
    )
    (net (code "105") (name "Net-(J1-ANT)") (class "Default")
      (node (ref "C13") (pin "1") (pinfunction "1_1") (pintype "passive"))
      (node (ref "C23") (pin "2") (pinfunction "2_2") (pintype "passive"))
      (node (ref "J1") (pin "1") (pinfunction "ANT_1") (pintype "passive"))
    )
    (net (code "106") (name "Net-(LED1-Pad2)") (class "Default")
      (node (ref "LED1") (pin "2") (pinfunction "2_2") (pintype "passive"))
      (node (ref "R1") (pin "2") (pinfunction "2_2") (pintype "passive"))
    )
    (net (code "107") (name "Net-(LED2-Pad1)") (class "Default")
      (node (ref "LED2") (pin "1") (pintype "passive"))
      (node (ref "R5") (pin "2") (pinfunction "2_2") (pintype "passive"))
    )
    (net (code "108") (name "Net-(Q1-B)") (class "Default")
      (node (ref "Q1") (pin "1") (pinfunction "B_1") (pintype "passive"))
      (node (ref "R8") (pin "7") (pinfunction "7_7") (pintype "passive"))
    )
    (net (code "109") (name "Net-(U1-PDR_ON)") (class "Default")
      (node (ref "R4") (pin "1") (pinfunction "1_1") (pintype "passive"))
      (node (ref "U1") (pin "143") (pinfunction "PDR_ON_143") (pintype "passive"))
    )
    (net (code "110") (name "Net-(U1-Vcap_1)") (class "Default")
      (node (ref "C9") (pin "2") (pinfunction "2_2") (pintype "passive"))
      (node (ref "U1") (pin "71") (pinfunction "Vcap_1_71") (pintype "passive"))
    )
    (net (code "111") (name "Net-(U1-Vcap_2)") (class "Default")
      (node (ref "C10") (pin "2") (pinfunction "2_2") (pintype "passive"))
      (node (ref "U1") (pin "106") (pinfunction "Vcap_2_106") (pintype "passive"))
    )
    (net (code "112") (name "Net-(U3-VDD)") (class "Default")
      (node (ref "C7") (pin "1") (pinfunction "1_1") (pintype "passive"))
      (node (ref "U3") (pin "6") (pinfunction "VDD_6") (pintype "passive"))
    )
    (net (code "113") (name "Net-(U8-B)") (class "Default")
      (node (ref "R8") (pin "1") (pinfunction "1_1") (pintype "passive"))
      (node (ref "U8") (pin "1") (pinfunction "B_1") (pintype "passive"))
    )
    (net (code "114") (name "Net-(U8-G)") (class "Default")
      (node (ref "R8") (pin "3") (pinfunction "3_3") (pintype "passive"))
      (node (ref "U8") (pin "3") (pinfunction "G_3") (pintype "passive"))
    )
    (net (code "115") (name "Net-(U8-R)") (class "Default")
      (node (ref "R8") (pin "5") (pinfunction "5_5") (pintype "passive"))
      (node (ref "U8") (pin "4") (pinfunction "R_4") (pintype "passive"))
    )
    (net (code "116") (name "POWER_5V_IN") (class "Default")
      (node (ref "F1") (pin "1") (pinfunction "1_1") (pintype "passive"))
      (node (ref "P4") (pin "19") (pinfunction "19_19") (pintype "passive"))
      (node (ref "U4") (pin "1") (pinfunction "VCC_1") (pintype "power_in"))
    )
    (net (code "117") (name "unconnected-(R10-BOT-Pad3)") (class "Default")
      (node (ref "R10") (pin "3") (pinfunction "BOT_3") (pintype "passive"))
    )
    (net (code "118") (name "unconnected-(U1-PA12{slash}TIM1_ETR{slash}U1_RTS{slash}CAN1_TX{slash}OTG_FS_DP-Pad104)") (class "Default")
      (node (ref "U1") (pin "104") (pinfunction "PA12/TIM1_ETR/U1_RTS/CAN1_TX/OTG_FS_DP_104") (pintype "passive"))
    )
    (net (code "119") (name "unconnected-(U1-PC10{slash}SPI3_SCK{slash}U3_TX{slash}U4_TX{slash}SDIO_D2{slash}DCMI_D8{slash}I2S3_CK-Pad111)") (class "Default")
      (node (ref "U1") (pin "111") (pinfunction "PC10/SPI3_SCK/U3_TX/U4_TX/SDIO_D2/DCMI_D8/I2S3_CK_111") (pintype "passive"))
    )
    (net (code "120") (name "unconnected-(U1-PC13{slash}RTC_AF1-Pad7)") (class "Default")
      (node (ref "U1") (pin "7") (pinfunction "PC13/RTC_AF1_7") (pintype "passive+no_connect"))
    )
    (net (code "121") (name "unconnected-(U1-PC14-OSC32_IN-Pad8)") (class "Default")
      (node (ref "U1") (pin "8") (pinfunction "PC14-OSC32_IN_8") (pintype "passive+no_connect"))
    )
    (net (code "122") (name "unconnected-(U1-PC15-OSC32_OUT-Pad9)") (class "Default")
      (node (ref "U1") (pin "9") (pinfunction "PC15-OSC32_OUT_9") (pintype "passive+no_connect"))
    )
    (net (code "123") (name "unconnected-(U1-PD5{slash}FSMC_NWE{slash}U2_TX-Pad119)") (class "Default")
      (node (ref "U1") (pin "119") (pinfunction "PD5/FSMC_NWE/U2_TX_119") (pintype "passive+no_connect"))
    )
    (net (code "124") (name "unconnected-(U1-PE4{slash}TRACED1{slash}FSMC_A20{slash}DCMI_D4-Pad3)") (class "Default")
      (node (ref "U1") (pin "3") (pinfunction "PE4/TRACED1/FSMC_A20/DCMI_D4_3") (pintype "passive"))
    )
    (net (code "125") (name "unconnected-(U1-PE7{slash}FSMC_D4{slash}TIM1_ETR-Pad58)") (class "Default")
      (node (ref "U1") (pin "58") (pinfunction "PE7/FSMC_D4/TIM1_ETR_58") (pintype "passive"))
    )
    (net (code "126") (name "unconnected-(U1-PE15{slash}FSMC_D12{slash}TIM1_BKIN-Pad68)") (class "Default")
      (node (ref "U1") (pin "68") (pinfunction "PE15/FSMC_D12/TIM1_BKIN_68") (pintype "passive"))
    )
    (net (code "127") (name "unconnected-(U1-PF2{slash}FSMC_A2{slash}I2C2_SMBA-Pad12)") (class "Default")
      (node (ref "U1") (pin "12") (pinfunction "PF2/FSMC_A2/I2C2_SMBA_12") (pintype "passive"))
    )
    (net (code "128") (name "unconnected-(U1-PF10{slash}FSMC_INTR{slash}ADC3_IN8-Pad22)") (class "Default")
      (node (ref "U1") (pin "22") (pinfunction "PF10/FSMC_INTR/ADC3_IN8_22") (pintype "passive"))
    )
    (net (code "129") (name "unconnected-(U1-PF11{slash}DCMI_D12-Pad49)") (class "Default")
      (node (ref "U1") (pin "49") (pinfunction "PF11/DCMI_D12_49") (pintype "passive"))
    )
    (net (code "130") (name "unconnected-(U1-PF12{slash}FSMC_A6-Pad50)") (class "Default")
      (node (ref "U1") (pin "50") (pinfunction "PF12/FSMC_A6_50") (pintype "passive"))
    )
    (net (code "131") (name "unconnected-(U1-PF13{slash}FSMC_A7-Pad53)") (class "Default")
      (node (ref "U1") (pin "53") (pinfunction "PF13/FSMC_A7_53") (pintype "passive"))
    )
    (net (code "132") (name "unconnected-(U1-PF14{slash}FSMC_A8-Pad54)") (class "Default")
      (node (ref "U1") (pin "54") (pinfunction "PF14/FSMC_A8_54") (pintype "passive"))
    )
    (net (code "133") (name "unconnected-(U1-PF15{slash}FSMC_A9-Pad55)") (class "Default")
      (node (ref "U1") (pin "55") (pinfunction "PF15/FSMC_A9_55") (pintype "passive"))
    )
    (net (code "134") (name "unconnected-(U1-PG0{slash}FSMC_A10-Pad56)") (class "Default")
      (node (ref "U1") (pin "56") (pinfunction "PG0/FSMC_A10_56") (pintype "passive"))
    )
    (net (code "135") (name "unconnected-(U1-PG1{slash}FSMC_A11-Pad57)") (class "Default")
      (node (ref "U1") (pin "57") (pinfunction "PG1/FSMC_A11_57") (pintype "passive"))
    )
    (net (code "136") (name "unconnected-(U1-PG2{slash}FSMC_A12-Pad87)") (class "Default")
      (node (ref "U1") (pin "87") (pinfunction "PG2/FSMC_A12_87") (pintype "passive"))
    )
    (net (code "137") (name "unconnected-(U1-PG4{slash}FSMC_A14-Pad89)") (class "Default")
      (node (ref "U1") (pin "89") (pinfunction "PG4/FSMC_A14_89") (pintype "passive"))
    )
    (net (code "138") (name "unconnected-(U1-PG5{slash}FSMC_A15-Pad90)") (class "Default")
      (node (ref "U1") (pin "90") (pinfunction "PG5/FSMC_A15_90") (pintype "passive"))
    )
    (net (code "139") (name "unconnected-(U1-PG6{slash}FSMC_INT2-Pad91)") (class "Default")
      (node (ref "U1") (pin "91") (pinfunction "PG6/FSMC_INT2_91") (pintype "passive"))
    )
    (net (code "140") (name "unconnected-(U1-PG7{slash}FSMC_INT3{slash}U6_CK-Pad92)") (class "Default")
      (node (ref "U1") (pin "92") (pinfunction "PG7/FSMC_INT3/U6_CK_92") (pintype "passive"))
    )
    (net (code "141") (name "unconnected-(U1-PG8{slash}U6_RTS{slash}ETH_PPS_OUT-Pad93)") (class "Default")
      (node (ref "U1") (pin "93") (pinfunction "PG8/U6_RTS/ETH_PPS_OUT_93") (pintype "passive"))
    )
    (net (code "142") (name "unconnected-(U1-PG14{slash}FSMC_A25{slash}U6_TX{slash}ETH_MII_TXD1{slash}ETH_RMII_TXD1-Pad129)") (class "Default")
      (node (ref "U1") (pin "129") (pinfunction "PG14/FSMC_A25/U6_TX/ETH_MII_TXD1/ETH_RMII_TXD1_129") (pintype "passive"))
    )
    (net (code "143") (name "unconnected-(U1-PG15{slash}U6_CTS{slash}DCMI_D13-Pad132)") (class "Default")
      (node (ref "U1") (pin "132") (pinfunction "PG15/U6_CTS/DCMI_D13_132") (pintype "passive"))
    )
    (net (code "144") (name "unconnected-(U3-CTS-Pad23)") (class "Default")
      (node (ref "U3") (pin "23") (pinfunction "CTS_23") (pintype "passive+no_connect"))
    )
    (net (code "145") (name "unconnected-(U3-DCO-Pad1)") (class "Default")
      (node (ref "U3") (pin "1") (pinfunction "DCO_1") (pintype "passive+no_connect"))
    )
    (net (code "146") (name "unconnected-(U3-DSR-Pad27)") (class "Default")
      (node (ref "U3") (pin "27") (pinfunction "DSR_27") (pintype "passive+no_connect"))
    )
    (net (code "147") (name "unconnected-(U3-DTR-Pad28)") (class "Default")
      (node (ref "U3") (pin "28") (pinfunction "DTR_28") (pintype "passive+no_connect"))
    )
    (net (code "148") (name "unconnected-(U3-NC-Pad10)") (class "Default")
      (node (ref "U3") (pin "10") (pinfunction "NC_10") (pintype "passive+no_connect"))
    )
    (net (code "149") (name "unconnected-(U3-NC-Pad13)") (class "Default")
      (node (ref "U3") (pin "13") (pinfunction "NC_13") (pintype "passive+no_connect"))
    )
    (net (code "150") (name "unconnected-(U3-NC-Pad14)") (class "Default")
      (node (ref "U3") (pin "14") (pinfunction "NC_14") (pintype "passive+no_connect"))
    )
    (net (code "151") (name "unconnected-(U3-NC-Pad15)") (class "Default")
      (node (ref "U3") (pin "15") (pinfunction "NC_15") (pintype "passive+no_connect"))
    )
    (net (code "152") (name "unconnected-(U3-NC-Pad16)") (class "Default")
      (node (ref "U3") (pin "16") (pinfunction "NC_16") (pintype "passive+no_connect"))
    )
    (net (code "153") (name "unconnected-(U3-NC-Pad17)") (class "Default")
      (node (ref "U3") (pin "17") (pinfunction "NC_17") (pintype "passive+no_connect"))
    )
    (net (code "154") (name "unconnected-(U3-NC-Pad19)") (class "Default")
      (node (ref "U3") (pin "19") (pinfunction "NC_19") (pintype "passive+no_connect"))
    )
    (net (code "155") (name "unconnected-(U3-NC-Pad20)") (class "Default")
      (node (ref "U3") (pin "20") (pinfunction "NC_20") (pintype "passive+no_connect"))
    )
    (net (code "156") (name "unconnected-(U3-NC-Pad21)") (class "Default")
      (node (ref "U3") (pin "21") (pinfunction "NC_21") (pintype "passive+no_connect"))
    )
    (net (code "157") (name "unconnected-(U3-NC-Pad22)") (class "Default")
      (node (ref "U3") (pin "22") (pinfunction "NC_22") (pintype "passive+no_connect"))
    )
    (net (code "158") (name "unconnected-(U3-RI-Pad2)") (class "Default")
      (node (ref "U3") (pin "2") (pinfunction "RI_2") (pintype "passive+no_connect"))
    )
    (net (code "159") (name "unconnected-(U3-RTS-Pad24)") (class "Default")
      (node (ref "U3") (pin "24") (pinfunction "RTS_24") (pintype "passive+no_connect"))
    )
    (net (code "160") (name "unconnected-(U3-SUS-Pad12)") (class "Default")
      (node (ref "U3") (pin "12") (pinfunction "SUS_12") (pintype "passive+no_connect"))
    )
    (net (code "161") (name "unconnected-(U3-VPP-Pad18)") (class "Default")
      (node (ref "U3") (pin "18") (pinfunction "VPP_18") (pintype "passive+no_connect"))
    )
    (net (code "162") (name "unconnected-(U4-ID-Pad4)") (class "Default")
      (node (ref "U4") (pin "4") (pinfunction "ID_4") (pintype "power_in"))
    )
    (net (code "163") (name "unconnected-(U5-D0-Pad1)") (class "Default")
      (node (ref "U5") (pin "1") (pinfunction "D0_1") (pintype "passive"))
    )
    (net (code "164") (name "unconnected-(U5-D1-Pad6)") (class "Default")
      (node (ref "U5") (pin "6") (pinfunction "D1_6") (pintype "passive"))
    )
    (net (code "165") (name "unconnected-(U5-D2-Pad12)") (class "Default")
      (node (ref "U5") (pin "12") (pinfunction "D2_12") (pintype "passive"))
    )
    (net (code "166") (name "unconnected-(U5-D3-Pad7)") (class "Default")
      (node (ref "U5") (pin "7") (pinfunction "D3_7") (pintype "passive"))
    )
    (net (code "167") (name "unconnected-(U7-GPIO1-Pad1)") (class "Default")
      (node (ref "U7") (pin "1") (pinfunction "GPIO1_1") (pintype "passive"))
    )
    (net (code "168") (name "unconnected-(U7-GPIO2-Pad2)") (class "Default")
      (node (ref "U7") (pin "2") (pinfunction "GPIO2_2") (pintype "passive"))
    )
    (net (code "169") (name "unconnected-(U7-GPIO3-Pad3)") (class "Default")
      (node (ref "U7") (pin "3") (pinfunction "GPIO3_3") (pintype "passive"))
    )
    (net (code "170") (name "unconnected-(U7-GPIO4-Pad4)") (class "Default")
      (node (ref "U7") (pin "4") (pinfunction "GPIO4_4") (pintype "passive"))
    )
    (net (code "171") (name "unconnected-(U7-UART0_CTS-Pad7)") (class "Default")
      (node (ref "U7") (pin "7") (pinfunction "UART0_CTS_7") (pintype "passive"))
    )
    (net (code "172") (name "unconnected-(U7-UART0_RTS-Pad8)") (class "Default")
      (node (ref "U7") (pin "8") (pinfunction "UART0_RTS_8") (pintype "passive"))
    )
    (net (code "173") (name "unconnected-(U7-WPS-Pad9)") (class "Default")
      (node (ref "U7") (pin "9") (pinfunction "WPS_9") (pintype "passive"))
    )
    (net (code "174") (name "unconnected-(U7-WPS-Pad14)") (class "Default")
      (node (ref "U7") (pin "14") (pinfunction "WPS_14") (pintype "passive"))
    )
    (net (code "175") (name "unconnected-(U7-nReady-Pad11)") (class "Default")
      (node (ref "U7") (pin "11") (pinfunction "nReady_11") (pintype "passive"))
    )
    (net (code "176") (name "unconnected-(U7-nReset-Pad10)") (class "Default")
      (node (ref "U7") (pin "10") (pinfunction "nReset_10") (pintype "passive"))
    )
  )
)
